# Power.net
KiCad netlist of a schematic drawn in Altium Designer
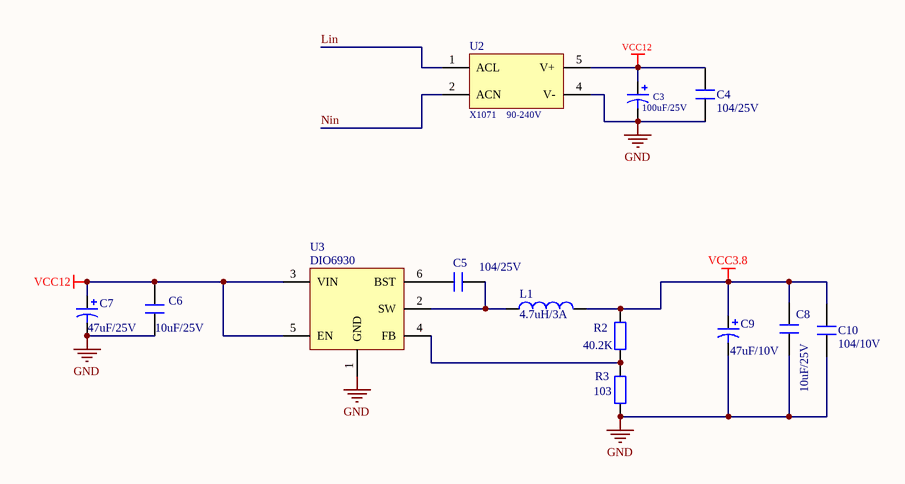
[diagram p0: Power.SchDoc]

(export (version "E")
  (design (tool "Eeschema 10.0.6"))
  (components
    (comp (ref "C3")
      (value "100uF/25V")
      (footprint "CAPPIND06")
      (description "Polarized Capacitor (Radial)")
      (fields (field (name "PUBLISHER") "Altium Limited"))
      (libsource (lib "Miscellaneous Devices") (part "Cap Pol1"))
    )
    (comp (ref "C4") (value "104/25V") (footprint "0603R") (libsource (lib "ES_Schematic") (part "CAP_1")))
    (comp (ref "C5") (value "104/25V") (footprint "0603R") (libsource (lib "ES_Schematic") (part "CAP_1")))
    (comp (ref "C6") (value "10uF/25V") (footprint "0603R") (libsource (lib "ES_Schematic") (part "CAP")))
    (comp (ref "C7")
      (value "47uF/25V")
      (footprint "0805R")
      (description "Polarized Capacitor (Radial)")
      (fields (field (name "PUBLISHER") "Altium Limited"))
      (libsource (lib "Miscellaneous Devices") (part "Cap Pol1"))
    )
    (comp (ref "C8") (value "10uF/25V") (footprint "0603R") (libsource (lib "ES_Schematic") (part "CAP")))
    (comp (ref "C9")
      (value "47uF/10V")
      (footprint "0805R")
      (description "Polarized Capacitor (Radial)")
      (fields (field (name "PUBLISHER") "Altium Limited"))
      (libsource (lib "Miscellaneous Devices") (part "Cap Pol1"))
    )
    (comp (ref "C10") (value "104/10V") (footprint "0603R") (libsource (lib "ES_Schematic") (part "CAP_1")))
    (comp (ref "L1")
      (value "4.7uH/3A")
      (footprint "贴片电感5020")
      (description "Inductor")
      (fields (field (name "PUBLISHER") "Altium Limited"))
      (libsource (lib "Miscellaneous Devices") (part "Inductor"))
    )
    (comp (ref "R2")
      (value "40.2K")
      (footprint "0603R")
      (description "Resistor")
      (fields (field (name "PUBLISHER") "Altium Limited"))
      (libsource (lib "Miscellaneous Devices") (part "Res2"))
    )
    (comp (ref "R3")
      (value "103")
      (footprint "0603R")
      (description "Resistor")
      (fields (field (name "PUBLISHER") "Altium Limited"))
      (libsource (lib "Miscellaneous Devices") (part "Res2"))
    )
    (comp (ref "U2")
      (value "X1071    90-240V")
      (footprint "X1071")
      (libsource (lib "sangjian") (part "AD2DC_EMC"))
    )
    (comp (ref "U3")
      (value "DIO6930")
      (footprint "SOT-23-6DBV")
      (libsource (lib "ES_Schematic") (part "BL8032"))
    )
  )
  (nets
    (net (code "1") (name "/Lin") (class "Default")
      (node (ref "U2") (pin "1") (pinfunction "ACL_1") (pintype "passive"))
    )
    (net (code "2") (name "/Nin") (class "Default")
      (node (ref "U2") (pin "2") (pinfunction "ACN_2") (pintype "passive"))
    )
    (net (code "3") (name "GND") (class "Default")
      (node (ref "C10") (pin "1") (pinfunction "1_1") (pintype "passive"))
      (node (ref "C3") (pin "2") (pinfunction "2_2") (pintype "passive"))
      (node (ref "C4") (pin "1") (pinfunction "1_1") (pintype "passive"))
      (node (ref "C6") (pin "1") (pinfunction "1_1") (pintype "passive"))
      (node (ref "C7") (pin "2") (pinfunction "2_2") (pintype "passive"))
      (node (ref "C8") (pin "1") (pinfunction "1_1") (pintype "passive"))
      (node (ref "C9") (pin "2") (pinfunction "2_2") (pintype "passive"))
      (node (ref "R3") (pin "2") (pinfunction "2_2") (pintype "passive"))
      (node (ref "U2") (pin "4") (pinfunction "V-_4") (pintype "passive"))
      (node (ref "U3") (pin "1") (pinfunction "GND_1") (pintype "passive"))
    )
    (net (code "4") (name "Net-(U3-BST)") (class "Default")
      (node (ref "C5") (pin "2") (pinfunction "2_2") (pintype "passive"))
      (node (ref "U3") (pin "6") (pinfunction "BST_6") (pintype "passive"))
    )
    (net (code "5") (name "Net-(U3-FB)") (class "Default")
      (node (ref "R2") (pin "2") (pinfunction "2_2") (pintype "passive"))
      (node (ref "R3") (pin "1") (pinfunction "1_1") (pintype "passive"))
      (node (ref "U3") (pin "4") (pinfunction "FB_4") (pintype "passive"))
    )
    (net (code "6") (name "Net-(U3-SW)") (class "Default")
      (node (ref "C5") (pin "1") (pinfunction "1_1") (pintype "passive"))
      (node (ref "L1") (pin "1") (pinfunction "1_1") (pintype "passive"))
      (node (ref "U3") (pin "2") (pinfunction "SW_2") (pintype "passive"))
    )
    (net (code "7") (name "VCC3.8") (class "Default")
      (node (ref "C10") (pin "2") (pinfunction "2_2") (pintype "passive"))
      (node (ref "C8") (pin "2") (pinfunction "2_2") (pintype "passive"))
      (node (ref "C9") (pin "1") (pinfunction "1_1") (pintype "passive"))
      (node (ref "L1") (pin "2") (pinfunction "2_2") (pintype "passive"))
      (node (ref "R2") (pin "1") (pinfunction "1_1") (pintype "passive"))
    )
    (net (code "8") (name "VCC12") (class "Default")
      (node (ref "C3") (pin "1") (pinfunction "1_1") (pintype "passive"))
      (node (ref "C4") (pin "2") (pinfunction "2_2") (pintype "passive"))
      (node (ref "C6") (pin "2") (pinfunction "2_2") (pintype "passive"))
      (node (ref "C7") (pin "1") (pinfunction "1_1") (pintype "passive"))
      (node (ref "U2") (pin "5") (pinfunction "V+_5") (pintype "passive"))
      (node (ref "U3") (pin "3") (pinfunction "VIN_3") (pintype "passive"))
      (node (ref "U3") (pin "5") (pinfunction "EN_5") (pintype "passive"))
    )
  )
)
